# lcd.net
KiCad netlist of a schematic drawn in EAGLE
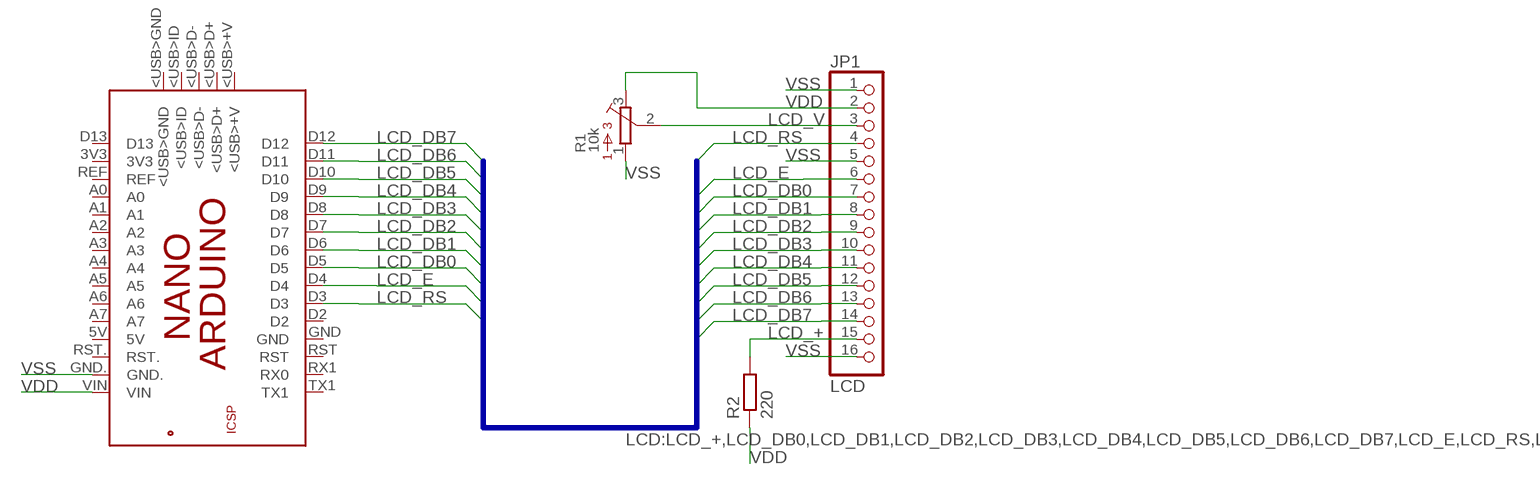
[diagram p0: schematic, sheet 1]

(export (version "E")
  (design (tool "Eeschema 10.0.6"))
  (components
    (comp (ref "JP1")
      (value "LCD")
      (footprint "eagle-import:1X16")
      (libsource (lib "eagle-import") (part "PINHD-1X16"))
    )
    (comp (ref "PCB1")
      (value "ARDUINO_NANO")
      (footprint "eagle-import:ARDUINO_NANO")
      (libsource (lib "eagle-import") (part "ARDUINO_NANO"))
    )
    (comp (ref "R1")
      (value "10k")
      (footprint "eagle-import:3362H")
      (libsource (lib "eagle-import") (part "3362H"))
    )
    (comp (ref "R2")
      (value "220")
      (footprint "eagle-import:0204_7")
      (libsource (lib "eagle-import") (part "R-EU_0204/7"))
    )
  )
  (nets
    (net (code "2") (name "/LCD_+") (class "Default")
      (node (ref "JP1") (pin "15") (pinfunction "15_15") (pintype "passive"))
      (node (ref "R2") (pin "2") (pinfunction "2_2") (pintype "passive"))
    )
    (net (code "3") (name "/LCD_DB0") (class "Default")
      (node (ref "JP1") (pin "7") (pinfunction "7_7") (pintype "passive"))
      (node (ref "PCB1") (pin "D5") (pinfunction "D5_D5") (pintype "bidirectional"))
    )
    (net (code "4") (name "/LCD_DB1") (class "Default")
      (node (ref "JP1") (pin "8") (pinfunction "8_8") (pintype "passive"))
      (node (ref "PCB1") (pin "D6") (pinfunction "D6_D6") (pintype "bidirectional"))
    )
    (net (code "5") (name "/LCD_DB2") (class "Default")
      (node (ref "JP1") (pin "9") (pinfunction "9_9") (pintype "passive"))
      (node (ref "PCB1") (pin "D7") (pinfunction "D7_D7") (pintype "bidirectional"))
    )
    (net (code "6") (name "/LCD_DB3") (class "Default")
      (node (ref "JP1") (pin "10") (pinfunction "10_10") (pintype "passive"))
      (node (ref "PCB1") (pin "D8") (pinfunction "D8_D8") (pintype "bidirectional"))
    )
    (net (code "7") (name "/LCD_DB4") (class "Default")
      (node (ref "JP1") (pin "11") (pinfunction "11_11") (pintype "passive"))
      (node (ref "PCB1") (pin "D9") (pinfunction "D9_D9") (pintype "bidirectional"))
    )
    (net (code "8") (name "/LCD_DB5") (class "Default")
      (node (ref "JP1") (pin "12") (pinfunction "12_12") (pintype "passive"))
      (node (ref "PCB1") (pin "D10") (pinfunction "D10_D10") (pintype "bidirectional"))
    )
    (net (code "9") (name "/LCD_DB6") (class "Default")
      (node (ref "JP1") (pin "13") (pinfunction "13_13") (pintype "passive"))
      (node (ref "PCB1") (pin "D11") (pinfunction "D11_D11") (pintype "bidirectional"))
    )
    (net (code "10") (name "/LCD_DB7") (class "Default")
      (node (ref "JP1") (pin "14") (pinfunction "14_14") (pintype "passive"))
      (node (ref "PCB1") (pin "D12") (pinfunction "D12_D12") (pintype "bidirectional"))
    )
    (net (code "11") (name "/LCD_E") (class "Default")
      (node (ref "JP1") (pin "6") (pinfunction "6_6") (pintype "passive"))
      (node (ref "PCB1") (pin "D4") (pinfunction "D4_D4") (pintype "bidirectional"))
    )
    (net (code "12") (name "/LCD_RS") (class "Default")
      (node (ref "JP1") (pin "4") (pinfunction "4_4") (pintype "passive"))
      (node (ref "PCB1") (pin "D3") (pinfunction "D3_D3") (pintype "bidirectional"))
    )
    (net (code "13") (name "/LCD_V") (class "Default")
      (node (ref "JP1") (pin "3") (pinfunction "3_3") (pintype "passive"))
      (node (ref "R1") (pin "2") (pinfunction "2_2") (pintype "passive"))
    )
    (net (code "14") (name "/VDD") (class "Default")
      (node (ref "JP1") (pin "2") (pinfunction "2_2") (pintype "passive"))
      (node (ref "PCB1") (pin "VIN") (pinfunction "VIN_VIN") (pintype "bidirectional"))
      (node (ref "R1") (pin "3") (pinfunction "3_3") (pintype "passive"))
      (node (ref "R2") (pin "1") (pinfunction "1_1") (pintype "passive"))
    )
    (net (code "15") (name "/VSS") (class "Default")
      (node (ref "JP1") (pin "1") (pinfunction "1_1") (pintype "passive"))
      (node (ref "JP1") (pin "16") (pinfunction "16_16") (pintype "passive"))
      (node (ref "JP1") (pin "5") (pinfunction "5_5") (pintype "passive"))
      (node (ref "PCB1") (pin "GND.") (pinfunction "GND._GND.") (pintype "bidirectional"))
      (node (ref "R1") (pin "1") (pinfunction "1_1") (pintype "passive"))
    )
    (net (code "17") (name "unconnected-(PCB1-Pad3V3)") (class "Default")
      (node (ref "PCB1") (pin "3V3") (pinfunction "3V3_3V3") (pintype "bidirectional"))
    )
    (net (code "18") (name "unconnected-(PCB1-Pad5V)") (class "Default")
      (node (ref "PCB1") (pin "5V") (pinfunction "5V_5V") (pintype "bidirectional"))
    )
    (net (code "19") (name "unconnected-(PCB1-Pad5V.)") (class "Default")
      (node (ref "PCB1") (pin "5V.") (pinfunction "5V._5V.") (pintype "bidirectional"))
    )
    (net (code "20") (name "unconnected-(PCB1-Pad<USB>+V)") (class "Default")
      (node (ref "PCB1") (pin "<USB>+V") (pinfunction "<USB>+V_<USB>+V") (pintype "bidirectional"))
    )
    (net (code "21") (name "unconnected-(PCB1-Pad<USB>D+)") (class "Default")
      (node (ref "PCB1") (pin "<USB>D+") (pinfunction "<USB>D+_<USB>D+") (pintype "bidirectional"))
    )
    (net (code "22") (name "unconnected-(PCB1-Pad<USB>D-)") (class "Default")
      (node (ref "PCB1") (pin "<USB>D-") (pinfunction "<USB>D-_<USB>D-") (pintype "bidirectional"))
    )
    (net (code "23") (name "unconnected-(PCB1-Pad<USB>GND)") (class "Default")
      (node (ref "PCB1") (pin "<USB>GND") (pinfunction "<USB>GND_<USB>GND") (pintype "bidirectional"))
    )
    (net (code "24") (name "unconnected-(PCB1-Pad<USB>ID)") (class "Default")
      (node (ref "PCB1") (pin "<USB>ID") (pinfunction "<USB>ID_<USB>ID") (pintype "bidirectional"))
    )
    (net (code "25") (name "unconnected-(PCB1-PadA0)") (class "Default")
      (node (ref "PCB1") (pin "A0") (pinfunction "A0_A0") (pintype "bidirectional"))
    )
    (net (code "26") (name "unconnected-(PCB1-PadA1)") (class "Default")
      (node (ref "PCB1") (pin "A1") (pinfunction "A1_A1") (pintype "bidirectional"))
    )
    (net (code "27") (name "unconnected-(PCB1-PadA2)") (class "Default")
      (node (ref "PCB1") (pin "A2") (pinfunction "A2_A2") (pintype "bidirectional"))
    )
    (net (code "28") (name "unconnected-(PCB1-PadA3)") (class "Default")
      (node (ref "PCB1") (pin "A3") (pinfunction "A3_A3") (pintype "bidirectional"))
    )
    (net (code "29") (name "unconnected-(PCB1-PadA4)") (class "Default")
      (node (ref "PCB1") (pin "A4") (pinfunction "A4_A4") (pintype "bidirectional"))
    )
    (net (code "30") (name "unconnected-(PCB1-PadA5)") (class "Default")
      (node (ref "PCB1") (pin "A5") (pinfunction "A5_A5") (pintype "bidirectional"))
    )
    (net (code "31") (name "unconnected-(PCB1-PadA6)") (class "Default")
      (node (ref "PCB1") (pin "A6") (pinfunction "A6_A6") (pintype "bidirectional"))
    )
    (net (code "32") (name "unconnected-(PCB1-PadA7)") (class "Default")
      (node (ref "PCB1") (pin "A7") (pinfunction "A7_A7") (pintype "bidirectional"))
    )
    (net (code "33") (name "unconnected-(PCB1-PadD2)") (class "Default")
      (node (ref "PCB1") (pin "D2") (pinfunction "D2_D2") (pintype "bidirectional"))
    )
    (net (code "34") (name "unconnected-(PCB1-PadD13)") (class "Default")
      (node (ref "PCB1") (pin "D13") (pinfunction "D13_D13") (pintype "bidirectional"))
    )
    (net (code "35") (name "unconnected-(PCB1-PadGND)") (class "Default")
      (node (ref "PCB1") (pin "GND") (pinfunction "GND_GND") (pintype "bidirectional"))
    )
    (net (code "36") (name "unconnected-(PCB1-PadGND_)") (class "Default")
      (node (ref "PCB1") (pin "GND_") (pinfunction "GND__GND_") (pintype "bidirectional"))
    )
    (net (code "37") (name "unconnected-(PCB1-PadMISO)") (class "Default")
      (node (ref "PCB1") (pin "MISO") (pinfunction "MISO_MISO") (pintype "bidirectional"))
    )
    (net (code "38") (name "unconnected-(PCB1-PadMOSI)") (class "Default")
      (node (ref "PCB1") (pin "MOSI") (pinfunction "MOSI_MOSI") (pintype "bidirectional"))
    )
    (net (code "39") (name "unconnected-(PCB1-PadREF)") (class "Default")
      (node (ref "PCB1") (pin "REF") (pinfunction "REF_REF") (pintype "bidirectional"))
    )
    (net (code "40") (name "unconnected-(PCB1-PadRESET..)") (class "Default")
      (node (ref "PCB1") (pin "RESET..") (pinfunction "RESET.._RESET..") (pintype "bidirectional"))
    )
    (net (code "41") (name "unconnected-(PCB1-PadRST)") (class "Default")
      (node (ref "PCB1") (pin "RST") (pinfunction "RST_RST") (pintype "bidirectional"))
    )
    (net (code "42") (name "unconnected-(PCB1-PadRST.)") (class "Default")
      (node (ref "PCB1") (pin "RST.") (pinfunction "RST._RST.") (pintype "bidirectional"))
    )
    (net (code "43") (name "unconnected-(PCB1-PadSCK)") (class "Default")
      (node (ref "PCB1") (pin "SCK") (pinfunction "SCK_SCK") (pintype "bidirectional"))
    )
    (net (code "44") (name "unconnected-(PCB1-PadTX1)") (class "Default")
      (node (ref "PCB1") (pin "TX1") (pinfunction "TX1_TX1") (pintype "bidirectional"))
    )
    (net (code "45") (name "unconnected-(PCB1-RX0-PadRX1)") (class "Default")
      (node (ref "PCB1") (pin "RX1") (pinfunction "RX0_RX1") (pintype "bidirectional"))
    )
  )
)
